# 48-24V_PDB.net
KiCad netlist of a schematic drawn in Altium Designer
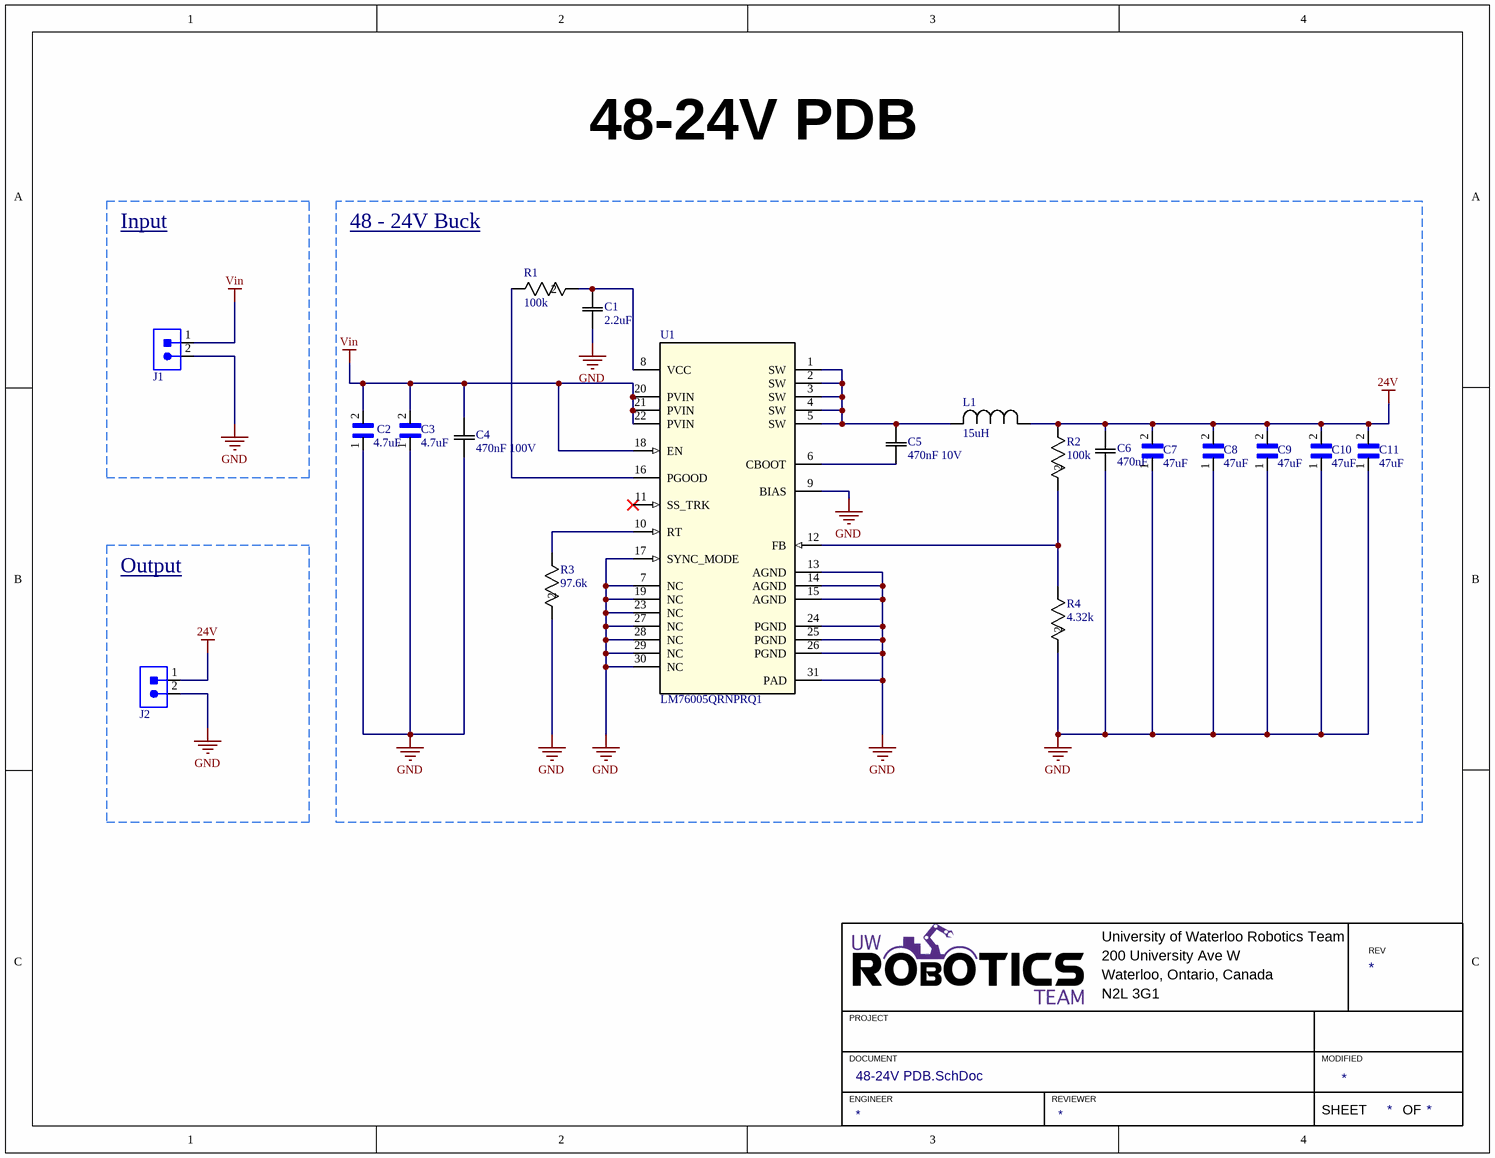
[diagram p0: 48-24V PDB.SchDoc]

(export (version "E")
  (design (tool "Eeschema 10.0.6"))
  (components
    (comp (ref "C1")
      (value "2.2uF")
      (footprint "CAP_1608_TDK")
      (description "No Description Available")
      (libsource (lib "UWRT_Schematic_Library_2020") (part "C1608X6S1C225K080AC"))
    )
    (comp (ref "C2")
      (value "4.7uF")
      (footprint "CAPC3216X190N")
      (description "SMD Capacitor X7S(EIA) with Capacitance: 4.7uF Tol. 20%. Rated Voltage: 100Vdc")
      (fields (field (name "MP") "GRM31CC72A475ME11L"))
      (libsource (lib "UWRT_Schematic_Library_2020") (part "GRM31CC72A475ME11L"))
    )
    (comp (ref "C3")
      (value "4.7uF")
      (footprint "CAPC3216X190N")
      (description "SMD Capacitor X7S(EIA) with Capacitance: 4.7uF Tol. 20%. Rated Voltage: 100Vdc")
      (fields (field (name "MP") "GRM31CC72A475ME11L"))
      (libsource (lib "UWRT_Schematic_Library_2020") (part "GRM31CC72A475ME11L"))
    )
    (comp (ref "C4")
      (value "470nF 100V")
      (footprint "CAP_2012_TDK")
      (description "No Description Available")
      (libsource (lib "UWRT_Schematic_Library_2020") (part "C2012X7S2A474K125AB"))
    )
    (comp (ref "C5")
      (value "470nF 10V")
      (footprint "G-155_MUR")
      (description "No Description Available")
      (libsource (lib "UWRT_Schematic_Library_2020") (part "GRM155R61A474KE15D"))
    )
    (comp (ref "C6")
      (value "470nF")
      (footprint "CAP_1608_TDK")
      (description "No Description Available")
      (libsource (lib "UWRT_Schematic_Library_2020") (part "C1608X7R1H474K080AC"))
    )
    (comp (ref "C7")
      (value "47uF")
      (footprint "CAPC6050X550N")
      (description "47 µF ±20% 50V Ceramic Capacitor X7R Stacked SMD, 2 J-Lead")
      (fields (field (name "MP") "CKG57NX7R1H476M500JH") (field (name "MF") "TDK Corporation"))
      (libsource (lib "UWRT_Schematic_Library_2020") (part "CKG57NX7R1H476M500JH"))
    )
    (comp (ref "C8")
      (value "47uF")
      (footprint "CAPC6050X550N")
      (description "47 µF ±20% 50V Ceramic Capacitor X7R Stacked SMD, 2 J-Lead")
      (fields (field (name "MP") "CKG57NX7R1H476M500JH") (field (name "MF") "TDK Corporation"))
      (libsource (lib "UWRT_Schematic_Library_2020") (part "CKG57NX7R1H476M500JH"))
    )
    (comp (ref "C9")
      (value "47uF")
      (footprint "CAPC6050X550N")
      (description "47 µF ±20% 50V Ceramic Capacitor X7R Stacked SMD, 2 J-Lead")
      (fields (field (name "MP") "CKG57NX7R1H476M500JH") (field (name "MF") "TDK Corporation"))
      (libsource (lib "UWRT_Schematic_Library_2020") (part "CKG57NX7R1H476M500JH"))
    )
    (comp (ref "C10")
      (value "47uF")
      (footprint "CAPC6050X550N")
      (description "47 µF ±20% 50V Ceramic Capacitor X7R Stacked SMD, 2 J-Lead")
      (fields (field (name "MP") "CKG57NX7R1H476M500JH") (field (name "MF") "TDK Corporation"))
      (libsource (lib "UWRT_Schematic_Library_2020") (part "CKG57NX7R1H476M500JH"))
    )
    (comp (ref "C11")
      (value "47uF")
      (footprint "CAPC6050X550N")
      (description "47 µF ±20% 50V Ceramic Capacitor X7R Stacked SMD, 2 J-Lead")
      (fields (field (name "MP") "CKG57NX7R1H476M500JH") (field (name "MF") "TDK Corporation"))
      (libsource (lib "UWRT_Schematic_Library_2020") (part "CKG57NX7R1H476M500JH"))
    )
    (comp (ref "J1")
      (value "CON_2POS_SCREW_TERM")
      (footprint "UWRT_Footprint_Library_2020:VP0265840000G")
      (description "PCB TERMINAL BLOCKS RISING CLAMP")
      (libsource (lib "UWRT_Schematic_Library_2020") (part "CON_2POS_SCREW_TERM_65A"))
    )
    (comp (ref "J2")
      (value "CON_2POS_SCREW_TERM")
      (footprint "UWRT_Footprint_Library_2020:VP0265840000G")
      (description "PCB TERMINAL BLOCKS RISING CLAMP")
      (libsource (lib "UWRT_Schematic_Library_2020") (part "CON_2POS_SCREW_TERM_65A"))
    )
    (comp (ref "L1")
      (value "15uH")
      (footprint "IND_1890_2-WE-HCI_WRE")
      (description "No Description Available")
      (libsource (lib "UWRT_Schematic_Library_2020") (part "74435571500"))
    )
    (comp (ref "R1")
      (value "100k")
      (footprint "RES_CRCW_0402_VIS")
      (description "No Description Available")
      (libsource (lib "UWRT_Schematic_Library_2020") (part "CRCW0402100KFKED"))
    )
    (comp (ref "R2")
      (value "100k")
      (footprint "RES_CRCW_0402_VIS")
      (description "No Description Available")
      (libsource (lib "UWRT_Schematic_Library_2020") (part "CRCW0402100KFKED"))
    )
    (comp (ref "R3")
      (value "97.6k")
      (footprint "RC0402N_VIS")
      (description "No Description Available")
      (libsource (lib "UWRT_Schematic_Library_2020") (part "CRCW040297K6FKED"))
    )
    (comp (ref "R4")
      (value "4.32k")
      (footprint "RC0603N_VIS")
      (description "No Description Available")
      (libsource (lib "UWRT_Schematic_Library_2020") (part "CRCW06034K32FKEA"))
    )
    (comp (ref "U1")
      (value "LM76005QRNPRQ1")
      (footprint "RNP0030A")
      (description "No Description Available")
      (libsource (lib "LM76005QRNPRQ1") (part "LM76005QRNPRQ1"))
    )
  )
  (nets
    (net (code "1") (name "24V") (class "Default")
      (node (ref "C10") (pin "2") (pinfunction "2_2") (pintype "passive"))
      (node (ref "C11") (pin "2") (pinfunction "2_2") (pintype "passive"))
      (node (ref "C6") (pin "2") (pinfunction "2_2") (pintype "passive"))
      (node (ref "C7") (pin "2") (pinfunction "2_2") (pintype "passive"))
      (node (ref "C8") (pin "2") (pinfunction "2_2") (pintype "passive"))
      (node (ref "C9") (pin "2") (pinfunction "2_2") (pintype "passive"))
      (node (ref "J2") (pin "1") (pinfunction "1_1") (pintype "passive"))
      (node (ref "L1") (pin "1") (pinfunction "1_1") (pintype "passive"))
      (node (ref "R2") (pin "1") (pinfunction "1_1") (pintype "passive"))
    )
    (net (code "2") (name "GND") (class "Default")
      (node (ref "C1") (pin "1") (pinfunction "1_1") (pintype "passive"))
      (node (ref "C10") (pin "1") (pinfunction "1_1") (pintype "passive"))
      (node (ref "C11") (pin "1") (pinfunction "1_1") (pintype "passive"))
      (node (ref "C2") (pin "1") (pinfunction "1_1") (pintype "passive"))
      (node (ref "C3") (pin "1") (pinfunction "1_1") (pintype "passive"))
      (node (ref "C4") (pin "1") (pinfunction "1_1") (pintype "passive"))
      (node (ref "C6") (pin "1") (pinfunction "1_1") (pintype "passive"))
      (node (ref "C7") (pin "1") (pinfunction "1_1") (pintype "passive"))
      (node (ref "C8") (pin "1") (pinfunction "1_1") (pintype "passive"))
      (node (ref "C9") (pin "1") (pinfunction "1_1") (pintype "passive"))
      (node (ref "J1") (pin "2") (pinfunction "2_2") (pintype "passive"))
      (node (ref "J2") (pin "2") (pinfunction "2_2") (pintype "passive"))
      (node (ref "R3") (pin "2") (pinfunction "2_2") (pintype "passive"))
      (node (ref "R4") (pin "2") (pinfunction "2_2") (pintype "passive"))
      (node (ref "U1") (pin "13") (pinfunction "AGND_13") (pintype "power_in"))
      (node (ref "U1") (pin "14") (pinfunction "AGND_14") (pintype "power_in"))
      (node (ref "U1") (pin "15") (pinfunction "AGND_15") (pintype "power_in"))
      (node (ref "U1") (pin "17") (pinfunction "SYNC_MODE_17") (pintype "input"))
      (node (ref "U1") (pin "19") (pinfunction "NC_19") (pintype "passive"))
      (node (ref "U1") (pin "23") (pinfunction "NC_23") (pintype "passive"))
      (node (ref "U1") (pin "24") (pinfunction "PGND_24") (pintype "power_in"))
      (node (ref "U1") (pin "25") (pinfunction "PGND_25") (pintype "power_in"))
      (node (ref "U1") (pin "26") (pinfunction "PGND_26") (pintype "power_in"))
      (node (ref "U1") (pin "27") (pinfunction "NC_27") (pintype "passive"))
      (node (ref "U1") (pin "28") (pinfunction "NC_28") (pintype "passive"))
      (node (ref "U1") (pin "29") (pinfunction "NC_29") (pintype "passive"))
      (node (ref "U1") (pin "30") (pinfunction "NC_30") (pintype "passive"))
      (node (ref "U1") (pin "31") (pinfunction "PAD_31") (pintype "power_in"))
      (node (ref "U1") (pin "7") (pinfunction "NC_7") (pintype "passive"))
      (node (ref "U1") (pin "9") (pinfunction "BIAS_9") (pintype "passive"))
    )
    (net (code "3") (name "Net-(C5-Pad2)") (class "Default")
      (node (ref "C5") (pin "2") (pinfunction "2_2") (pintype "passive"))
      (node (ref "L1") (pin "2") (pinfunction "2_2") (pintype "passive"))
      (node (ref "U1") (pin "1") (pinfunction "SW_1") (pintype "power_in"))
      (node (ref "U1") (pin "2") (pinfunction "SW_2") (pintype "power_in"))
      (node (ref "U1") (pin "3") (pinfunction "SW_3") (pintype "power_in"))
      (node (ref "U1") (pin "4") (pinfunction "SW_4") (pintype "power_in"))
      (node (ref "U1") (pin "5") (pinfunction "SW_5") (pintype "power_in"))
    )
    (net (code "4") (name "Net-(U1-CBOOT)") (class "Default")
      (node (ref "C5") (pin "1") (pinfunction "1_1") (pintype "passive"))
      (node (ref "U1") (pin "6") (pinfunction "CBOOT_6") (pintype "power_in"))
    )
    (net (code "5") (name "Net-(U1-FB)") (class "Default")
      (node (ref "R2") (pin "2") (pinfunction "2_2") (pintype "passive"))
      (node (ref "R4") (pin "1") (pinfunction "1_1") (pintype "passive"))
      (node (ref "U1") (pin "12") (pinfunction "FB_12") (pintype "input"))
    )
    (net (code "6") (name "Net-(U1-PGOOD)") (class "Default")
      (node (ref "R1") (pin "1") (pinfunction "1_1") (pintype "passive"))
      (node (ref "U1") (pin "16") (pinfunction "PGOOD_16") (pintype "open_collector"))
    )
    (net (code "7") (name "Net-(U1-RT)") (class "Default")
      (node (ref "R3") (pin "1") (pinfunction "1_1") (pintype "passive"))
      (node (ref "U1") (pin "10") (pinfunction "RT_10") (pintype "input"))
    )
    (net (code "8") (name "Net-(U1-VCC)") (class "Default")
      (node (ref "C1") (pin "2") (pinfunction "2_2") (pintype "passive"))
      (node (ref "R1") (pin "2") (pinfunction "2_2") (pintype "passive"))
      (node (ref "U1") (pin "8") (pinfunction "VCC_8") (pintype "power_in"))
    )
    (net (code "9") (name "Vin") (class "Default")
      (node (ref "C2") (pin "2") (pinfunction "2_2") (pintype "passive"))
      (node (ref "C3") (pin "2") (pinfunction "2_2") (pintype "passive"))
      (node (ref "C4") (pin "2") (pinfunction "2_2") (pintype "passive"))
      (node (ref "J1") (pin "1") (pinfunction "1_1") (pintype "passive"))
      (node (ref "U1") (pin "18") (pinfunction "EN_18") (pintype "input"))
      (node (ref "U1") (pin "20") (pinfunction "PVIN_20") (pintype "power_in"))
      (node (ref "U1") (pin "21") (pinfunction "PVIN_21") (pintype "power_in"))
      (node (ref "U1") (pin "22") (pinfunction "PVIN_22") (pintype "power_in"))
    )
    (net (code "10") (name "unconnected-(U1-SS_TRK-Pad11)") (class "Default")
      (node (ref "U1") (pin "11") (pinfunction "SS_TRK_11") (pintype "input+no_connect"))
    )
  )
)
